# UBC-Thunderbots_PCB_Power__power-v3_1_pc.net
KiCad netlist of a schematic drawn in Altium Designer
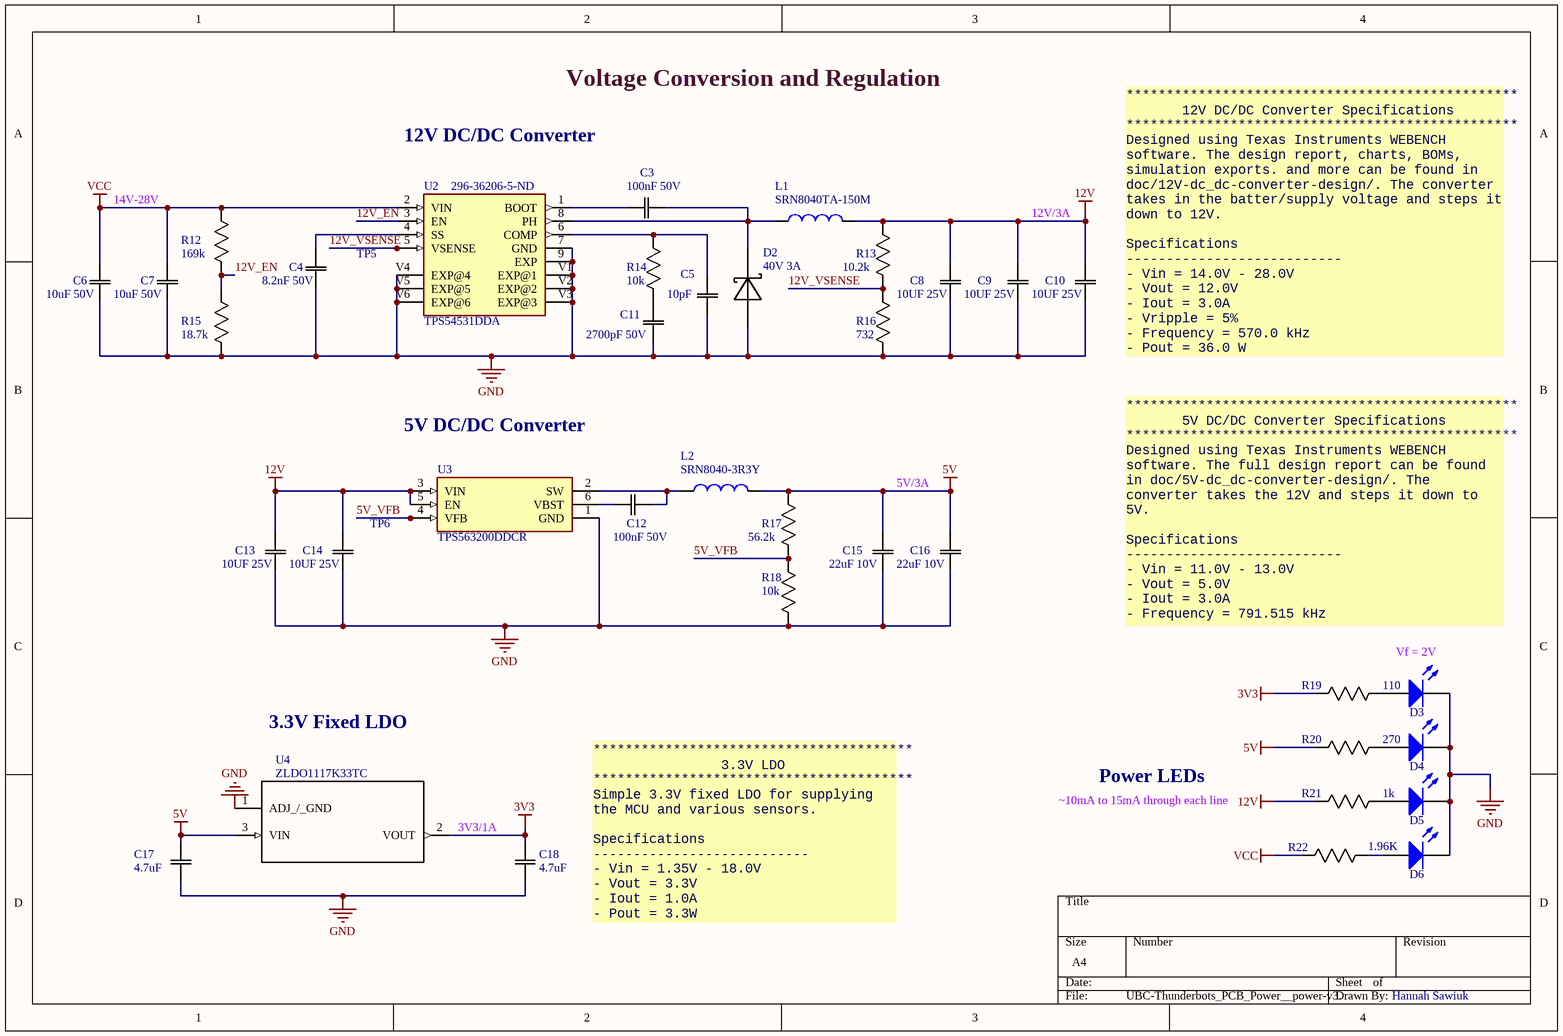
[diagram p0: UBC-Thunderbots_PCB_Power__power-v3.1_pcb__regulation.SchDoc]

(export (version "E")
  (design (tool "Eeschema 10.0.6"))
  (components
    (comp (ref "C3")
      (value "100nF 50V")
      (footprint "0805")
      (description "CAP CER 0.1UF 50V X7R 0805")
      (fields (field (name "TOLERANCE") "10%"))
      (libsource (lib "AltiumLibraries") (part "CAP 100nF 50V"))
    )
    (comp (ref "C4")
      (value "8.2nF 50V")
      (footprint "0805")
      (description "CAP CER 8200PF 50V X7R 0805")
      (fields (field (name "TOLERANCE") "10%"))
      (libsource (lib "AltiumLibraries") (part "CAP 8.2nF 50V"))
    )
    (comp (ref "C5")
      (value "10pF")
      (footprint "0805")
      (description "CAP CER 10PF 50V X7R 0603/0805")
      (fields (field (name "TOLERANCE") "10%"))
      (libsource (lib "AltiumLibraries") (part "CAP 10pF 50V"))
    )
    (comp (ref "C6")
      (value "10uF 50V")
      (footprint "1210")
      (description "CAP CER 10UF 50V X7R")
      (fields (field (name "TOLERANCE") "10%"))
      (libsource (lib "AltiumLibraries") (part "CAP 10uF 50V"))
    )
    (comp (ref "C7")
      (value "10uF 50V")
      (footprint "1210")
      (description "CAP CER 10UF 50V X7R")
      (fields (field (name "TOLERANCE") "10%"))
      (libsource (lib "AltiumLibraries") (part "CAP 10uF 50V"))
    )
    (comp (ref "C8")
      (value "10UF 25V")
      (footprint "1206")
      (description "CAP CER 10UF 25V X5R 1206")
      (fields (field (name "TOLERANCE") "10%"))
      (libsource (lib "AltiumLibraries") (part "CAP 10uF 25V"))
    )
    (comp (ref "C9")
      (value "10UF 25V")
      (footprint "1206")
      (description "CAP CER 10UF 25V X5R 1206")
      (fields (field (name "TOLERANCE") "10%"))
      (libsource (lib "AltiumLibraries") (part "CAP 10uF 25V"))
    )
    (comp (ref "C10")
      (value "10UF 25V")
      (footprint "1206")
      (description "CAP CER 10UF 25V X5R 1206")
      (fields (field (name "TOLERANCE") "10%"))
      (libsource (lib "AltiumLibraries") (part "CAP 10uF 25V"))
    )
    (comp (ref "C11")
      (value "2700pF 50V")
      (footprint "0805")
      (description "CAP CER 2700PF 50V X7R 0805")
      (fields (field (name "TOLERANCE") "10%"))
      (libsource (lib "AltiumLibraries") (part "CAP 2700pF 50V"))
    )
    (comp (ref "C12")
      (value "100nF 50V")
      (footprint "0805")
      (description "CAP CER 0.1UF 50V X7R 0805")
      (fields (field (name "TOLERANCE") "10%"))
      (libsource (lib "AltiumLibraries") (part "CAP 100nF 50V"))
    )
    (comp (ref "C13")
      (value "10UF 25V")
      (footprint "1206")
      (description "CAP CER 10UF 25V X5R 1206")
      (fields (field (name "TOLERANCE") "10%"))
      (libsource (lib "AltiumLibraries") (part "CAP 10uF 25V"))
    )
    (comp (ref "C14")
      (value "10UF 25V")
      (footprint "1206")
      (description "CAP CER 10UF 25V X5R 1206")
      (fields (field (name "TOLERANCE") "10%"))
      (libsource (lib "AltiumLibraries") (part "CAP 10uF 25V"))
    )
    (comp (ref "C15")
      (value "22uF 10V")
      (footprint "0805")
      (description "CAP CER 2.2UF 10V X5R 0805")
      (fields (field (name "TOLERANCE") "20%"))
      (libsource (lib "AltiumLibraries") (part "CAP 22uF 10V"))
    )
    (comp (ref "C16")
      (value "22uF 10V")
      (footprint "0805")
      (description "CAP CER 2.2UF 10V X5R 0805")
      (fields (field (name "TOLERANCE") "20%"))
      (libsource (lib "AltiumLibraries") (part "CAP 22uF 10V"))
    )
    (comp (ref "C17")
      (value "4.7uF")
      (footprint "0805")
      (description "CAP CER 4.7UF 6.3V X5R 0603/0805")
      (fields (field (name "TOLERANCE") "10%"))
      (libsource (lib "AltiumLibraries") (part "CAP 4.7uF 6.3V"))
    )
    (comp (ref "C18")
      (value "4.7uF")
      (footprint "0805")
      (description "CAP CER 4.7UF 6.3V X5R 0603/0805")
      (fields (field (name "TOLERANCE") "10%"))
      (libsource (lib "AltiumLibraries") (part "CAP 4.7uF 6.3V"))
    )
    (comp (ref "D2")
      (value "40V 3A")
      (footprint "DO-214AC")
      (description "Diode Schottky 40V 3A Surface Mount SMA")
      (libsource (lib "AltiumLibraries") (part "DIODE SCHOTTKY 40V 3A"))
    )
    (comp (ref "D3")
      (value "LED2")
      (footprint "3.2X1.6X1.1")
      (description "Typical RED, GREEN, YELLOW, AMBER GaAs LED")
      (libsource (lib "AltiumLibraries") (part "LED GREEN SMD"))
    )
    (comp (ref "D4")
      (value "LED2")
      (footprint "3.2X1.6X1.1")
      (description "Typical RED, GREEN, YELLOW, AMBER GaAs LED")
      (libsource (lib "AltiumLibraries") (part "LED GREEN SMD"))
    )
    (comp (ref "D5")
      (value "LED2")
      (footprint "3.2X1.6X1.1")
      (description "Typical RED, GREEN, YELLOW, AMBER GaAs LED")
      (libsource (lib "AltiumLibraries") (part "LED GREEN SMD"))
    )
    (comp (ref "D6")
      (value "LED2")
      (footprint "3.2X1.6X1.1")
      (description "Typical RED, GREEN, YELLOW, AMBER GaAs LED")
      (libsource (lib "AltiumLibraries") (part "LED GREEN SMD"))
    )
    (comp (ref "L1")
      (value "SRN8040TA-150M")
      (footprint "INDP8279X40M")
      (description "15µH Semi-Shielded Wirewound Inductor 2.4A 70mOhm Max Nonstandard")
      (fields (field (name "MF") "Bourns Inc."))
      (libsource (lib "AltiumLibraries") (part "IND 15UH 3.2A 50 MOHM"))
    )
    (comp (ref "L2")
      (value "SRN8040-3R3Y")
      (footprint "INDP8279X40M")
      (description "3.3µH Semi-Shielded Wirewound Inductor 5.6A 21mOhm Max Nonstandard")
      (fields (field (name "MF") "Bourns Inc."))
      (libsource (lib "AltiumLibraries") (part "IND 3.3UH 5.6A 21 MOHM SMD"))
    )
    (comp (ref "R12")
      (value "169k")
      (footprint "0805")
      (description "RES SMD 169K OHM 1% 1/8W 0805")
      (fields (field (name "TOLERANCE") "1%"))
      (libsource (lib "AltiumLibraries") (part "RES 169k 1/8W"))
    )
    (comp (ref "R13")
      (value "10.2k")
      (footprint "0805")
      (description "RES SMD 10.2K OHM 1% 1/8W 0805")
      (fields (field (name "TOLERANCE") "1%"))
      (libsource (lib "AltiumLibraries") (part "RES 10.2k 1/8W"))
    )
    (comp (ref "R14")
      (value "10k")
      (footprint "0805")
      (description "RES SMD 10K OHM 1% 1/8W 0805")
      (fields (field (name "TOLERANCE") "1%"))
      (libsource (lib "AltiumLibraries") (part "RES 10k 1/8W - 1%"))
    )
    (comp (ref "R15")
      (value "18.7k")
      (footprint "0805")
      (description "RES SMD 18.7K OHM 1% 1/8W 0805")
      (fields (field (name "TOLERANCE") "1%"))
      (libsource (lib "AltiumLibraries") (part "RES 18.7K 1/8W"))
    )
    (comp (ref "R16")
      (value "732")
      (footprint "0805")
      (description "RES SMD 732 OHM 1% 1/8W 0805")
      (fields (field (name "TOLERANCE") "1%"))
      (libsource (lib "AltiumLibraries") (part "RES 732.0 1/8W"))
    )
    (comp (ref "R17")
      (value "56.2k")
      (footprint "0805")
      (description "RES SMD 56.2K OHM 1% 1/10W 0603")
      (fields (field (name "TOLERANCE") "1%"))
      (libsource (lib "AltiumLibraries") (part "RES 56.2k 1/10W"))
    )
    (comp (ref "R18")
      (value "10k")
      (footprint "0805")
      (description "RES SMD 10K OHM 1% 1/8W 0805")
      (fields (field (name "TOLERANCE") "1%"))
      (libsource (lib "AltiumLibraries") (part "RES 10k 1/8W - 1%"))
    )
    (comp (ref "R19")
      (value "110")
      (footprint "0805")
      (description "RES SMD 110 OHM 1% 1/8W 0805")
      (fields (field (name "TOLERANCE") "1%"))
      (libsource (lib "AltiumLibraries") (part "RES 110.0 1/8W - 1%"))
    )
    (comp (ref "R20")
      (value "270")
      (footprint "0805")
      (description "RES SMD 270 OHM 5% 1/8W 0805")
      (fields (field (name "TOLERANCE") "5%"))
      (libsource (lib "AltiumLibraries") (part "RES 270.0 1/8W"))
    )
    (comp (ref "R21")
      (value "1k")
      (footprint "0805")
      (description "RES SMD 1K OHM 5% 1/8W 0805")
      (fields (field (name "TOLERANCE") "5%"))
      (libsource (lib "AltiumLibraries") (part "RES 1k 1/8W"))
    )
    (comp (ref "R22")
      (value "1.96K")
      (footprint "0805")
      (description "RES SMD 1.96K OHM 1% 1/8W 0805")
      (fields (field (name "TOLERANCE") "1%"))
      (libsource (lib "AltiumLibraries") (part "RES 1.96k 1/8W"))
    )
    (comp (ref "TP5")
      (value "Test Point (Via)")
      (footprint "TP")
      (libsource (lib "AltiumLibraries") (part "Test Point (Via)"))
    )
    (comp (ref "TP6")
      (value "Test Point (Via)")
      (footprint "TP")
      (libsource (lib "AltiumLibraries") (part "Test Point (Via)"))
    )
    (comp (ref "U2")
      (value "TPS54531DDA")
      (footprint "8-PowerSOIC")
      (description "Buck Switching Regulator IC Positive Adjustable 0.8V 1 Output 5A 8-PowerSOIC _0.154, 3.90mm Width_")
      (fields
        (field (name "MF") "Texas Instruments")
        (field (name "SUPPLIER PART NUMBER 1") "296-36206-5-ND")
      )
      (libsource (lib "AltiumLibraries") (part "TPS54531DDA"))
    )
    (comp (ref "U3")
      (value "TPS563200DDCR")
      (footprint "TSOT-23-6")
      (description "Buck Switching Regulator IC Positive Adjustable 0.76V 1 Output 3A SOT-23-6 Thin, TSOT-23-6")
      (fields (field (name "MF") "Texas Instruments"))
      (libsource (lib "AltiumLibraries") (part "TPS563200DDCR"))
    )
    (comp (ref "U4")
      (value "ZLDO1117K33TC")
      (footprint "DPAK (TO-252)")
      (description "Linear Voltage Regulator IC Positive Fixed 1 Output  1A TO-252-3")
      (fields (field (name "MF") "Diodes Incorporated"))
      (libsource (lib "AltiumLibraries") (part "ZLDO1117K33TC"))
    )
  )
  (nets
    (net (code "1") (name "/5V_VFB") (class "Default")
      (node (ref "R17") (pin "2") (pinfunction "R2_2") (pintype "passive"))
      (node (ref "R18") (pin "2") (pinfunction "R2_2") (pintype "passive"))
      (node (ref "TP6") (pin "1") (pinfunction "1_1") (pintype "passive"))
      (node (ref "U3") (pin "4") (pinfunction "VFB_4") (pintype "input"))
    )
    (net (code "2") (name "/12V_EN") (class "Default")
      (node (ref "R12") (pin "2") (pinfunction "R2_2") (pintype "passive"))
      (node (ref "R15") (pin "1") (pinfunction "R1_1") (pintype "passive"))
      (node (ref "U2") (pin "3") (pinfunction "EN_3") (pintype "input"))
    )
    (net (code "3") (name "/12V_VSENSE") (class "Default")
      (node (ref "R13") (pin "1") (pinfunction "R1_1") (pintype "passive"))
      (node (ref "R16") (pin "2") (pinfunction "R2_2") (pintype "passive"))
      (node (ref "TP5") (pin "1") (pinfunction "1_1") (pintype "passive"))
      (node (ref "U2") (pin "5") (pinfunction "VSENSE_5") (pintype "input"))
    )
    (net (code "4") (name "3V3") (class "Default")
      (node (ref "C18") (pin "1") (pinfunction "C1_1") (pintype "passive"))
      (node (ref "R19") (pin "1") (pinfunction "R1_1") (pintype "passive"))
      (node (ref "U4") (pin "2") (pinfunction "VOUT_2") (pintype "output"))
    )
    (net (code "5") (name "5V") (class "Default")
      (node (ref "C15") (pin "2") (pinfunction "C2_2") (pintype "passive"))
      (node (ref "C16") (pin "2") (pinfunction "C2_2") (pintype "passive"))
      (node (ref "C17") (pin "1") (pinfunction "C1_1") (pintype "passive"))
      (node (ref "L2") (pin "2") (pinfunction "2_2") (pintype "passive"))
      (node (ref "R17") (pin "1") (pinfunction "R1_1") (pintype "passive"))
      (node (ref "R20") (pin "1") (pinfunction "R1_1") (pintype "passive"))
      (node (ref "U4") (pin "3") (pinfunction "VIN_3") (pintype "input"))
    )
    (net (code "6") (name "12V") (class "Default")
      (node (ref "C10") (pin "2") (pinfunction "C2_2") (pintype "passive"))
      (node (ref "C13") (pin "2") (pinfunction "C2_2") (pintype "passive"))
      (node (ref "C14") (pin "2") (pinfunction "C2_2") (pintype "passive"))
      (node (ref "C8") (pin "2") (pinfunction "C2_2") (pintype "passive"))
      (node (ref "C9") (pin "2") (pinfunction "C2_2") (pintype "passive"))
      (node (ref "L1") (pin "2") (pinfunction "2_2") (pintype "passive"))
      (node (ref "R13") (pin "2") (pinfunction "R2_2") (pintype "passive"))
      (node (ref "R21") (pin "1") (pinfunction "R1_1") (pintype "passive"))
      (node (ref "U3") (pin "3") (pinfunction "VIN_3") (pintype "input"))
      (node (ref "U3") (pin "5") (pinfunction "EN_5") (pintype "input"))
    )
    (net (code "7") (name "GND") (class "Default")
      (node (ref "C10") (pin "1") (pinfunction "C1_1") (pintype "passive"))
      (node (ref "C11") (pin "1") (pinfunction "C1_1") (pintype "passive"))
      (node (ref "C13") (pin "1") (pinfunction "C1_1") (pintype "passive"))
      (node (ref "C14") (pin "1") (pinfunction "C1_1") (pintype "passive"))
      (node (ref "C15") (pin "1") (pinfunction "C1_1") (pintype "passive"))
      (node (ref "C16") (pin "1") (pinfunction "C1_1") (pintype "passive"))
      (node (ref "C17") (pin "2") (pinfunction "C2_2") (pintype "passive"))
      (node (ref "C18") (pin "2") (pinfunction "C2_2") (pintype "passive"))
      (node (ref "C4") (pin "1") (pinfunction "C1_1") (pintype "passive"))
      (node (ref "C5") (pin "1") (pinfunction "C1_1") (pintype "passive"))
      (node (ref "C6") (pin "1") (pinfunction "C1_1") (pintype "passive"))
      (node (ref "C7") (pin "1") (pinfunction "C1_1") (pintype "passive"))
      (node (ref "C8") (pin "1") (pinfunction "C1_1") (pintype "passive"))
      (node (ref "C9") (pin "1") (pinfunction "C1_1") (pintype "passive"))
      (node (ref "D2") (pin "A") (pinfunction "A_A") (pintype "passive"))
      (node (ref "D3") (pin "2") (pinfunction "K_2") (pintype "passive"))
      (node (ref "D4") (pin "2") (pinfunction "K_2") (pintype "passive"))
      (node (ref "D5") (pin "2") (pinfunction "K_2") (pintype "passive"))
      (node (ref "D6") (pin "2") (pinfunction "K_2") (pintype "passive"))
      (node (ref "R15") (pin "2") (pinfunction "R2_2") (pintype "passive"))
      (node (ref "R16") (pin "1") (pinfunction "R1_1") (pintype "passive"))
      (node (ref "R18") (pin "1") (pinfunction "R1_1") (pintype "passive"))
      (node (ref "U2") (pin "7") (pinfunction "GND_7") (pintype "power_in"))
      (node (ref "U2") (pin "9") (pinfunction "EXP_9") (pintype "power_in"))
      (node (ref "U2") (pin "V1") (pinfunction "EXP@1_V1") (pintype "power_in"))
      (node (ref "U2") (pin "V2") (pinfunction "EXP@2_V2") (pintype "power_in"))
      (node (ref "U2") (pin "V3") (pinfunction "EXP@3_V3") (pintype "power_in"))
      (node (ref "U2") (pin "V4") (pinfunction "EXP@4_V4") (pintype "power_in"))
      (node (ref "U2") (pin "V5") (pinfunction "EXP@5_V5") (pintype "power_in"))
      (node (ref "U2") (pin "V6") (pinfunction "EXP@6_V6") (pintype "power_in"))
      (node (ref "U3") (pin "1") (pinfunction "GND_1") (pintype "power_in"))
      (node (ref "U4") (pin "1") (pinfunction "ADJ_/_GND_1") (pintype "power_in"))
    )
    (net (code "8") (name "Net-(C3-C1)") (class "Default")
      (node (ref "C3") (pin "1") (pinfunction "C1_1") (pintype "passive"))
      (node (ref "U2") (pin "1") (pinfunction "BOOT_1") (pintype "output"))
    )
    (net (code "9") (name "Net-(C3-C2)") (class "Default")
      (node (ref "C3") (pin "2") (pinfunction "C2_2") (pintype "passive"))
      (node (ref "D2") (pin "C") (pinfunction "K_C") (pintype "passive"))
      (node (ref "L1") (pin "1") (pinfunction "1_1") (pintype "passive"))
      (node (ref "U2") (pin "8") (pinfunction "PH_8") (pintype "output"))
    )
    (net (code "10") (name "Net-(C4-C2)") (class "Default")
      (node (ref "C4") (pin "2") (pinfunction "C2_2") (pintype "passive"))
      (node (ref "U2") (pin "4") (pinfunction "SS_4") (pintype "input"))
    )
    (net (code "11") (name "Net-(C5-C2)") (class "Default")
      (node (ref "C5") (pin "2") (pinfunction "C2_2") (pintype "passive"))
      (node (ref "R14") (pin "1") (pinfunction "R1_1") (pintype "passive"))
      (node (ref "U2") (pin "6") (pinfunction "COMP_6") (pintype "output"))
    )
    (net (code "12") (name "Net-(C11-C2)") (class "Default")
      (node (ref "C11") (pin "2") (pinfunction "C2_2") (pintype "passive"))
      (node (ref "R14") (pin "2") (pinfunction "R2_2") (pintype "passive"))
    )
    (net (code "13") (name "Net-(C12-C1)") (class "Default")
      (node (ref "C12") (pin "1") (pinfunction "C1_1") (pintype "passive"))
      (node (ref "U3") (pin "6") (pinfunction "VBST_6") (pintype "passive"))
    )
    (net (code "14") (name "Net-(C12-C2)") (class "Default")
      (node (ref "C12") (pin "2") (pinfunction "C2_2") (pintype "passive"))
      (node (ref "L2") (pin "1") (pinfunction "1_1") (pintype "passive"))
      (node (ref "U3") (pin "2") (pinfunction "SW_2") (pintype "passive"))
    )
    (net (code "15") (name "Net-(D3-A)") (class "Default")
      (node (ref "D3") (pin "1") (pinfunction "A_1") (pintype "passive"))
      (node (ref "R19") (pin "2") (pinfunction "R2_2") (pintype "passive"))
    )
    (net (code "16") (name "Net-(D4-A)") (class "Default")
      (node (ref "D4") (pin "1") (pinfunction "A_1") (pintype "passive"))
      (node (ref "R20") (pin "2") (pinfunction "R2_2") (pintype "passive"))
    )
    (net (code "17") (name "Net-(D5-A)") (class "Default")
      (node (ref "D5") (pin "1") (pinfunction "A_1") (pintype "passive"))
      (node (ref "R21") (pin "2") (pinfunction "R2_2") (pintype "passive"))
    )
    (net (code "18") (name "Net-(D6-A)") (class "Default")
      (node (ref "D6") (pin "1") (pinfunction "A_1") (pintype "passive"))
      (node (ref "R22") (pin "2") (pinfunction "R2_2") (pintype "passive"))
    )
    (net (code "19") (name "VCC") (class "Default")
      (node (ref "C6") (pin "2") (pinfunction "C2_2") (pintype "passive"))
      (node (ref "C7") (pin "2") (pinfunction "C2_2") (pintype "passive"))
      (node (ref "R12") (pin "1") (pinfunction "R1_1") (pintype "passive"))
      (node (ref "R22") (pin "1") (pinfunction "R1_1") (pintype "passive"))
      (node (ref "U2") (pin "2") (pinfunction "VIN_2") (pintype "input"))
    )
  )
)
